# schematic1.net
KiCad netlist of a schematic drawn in EAGLE
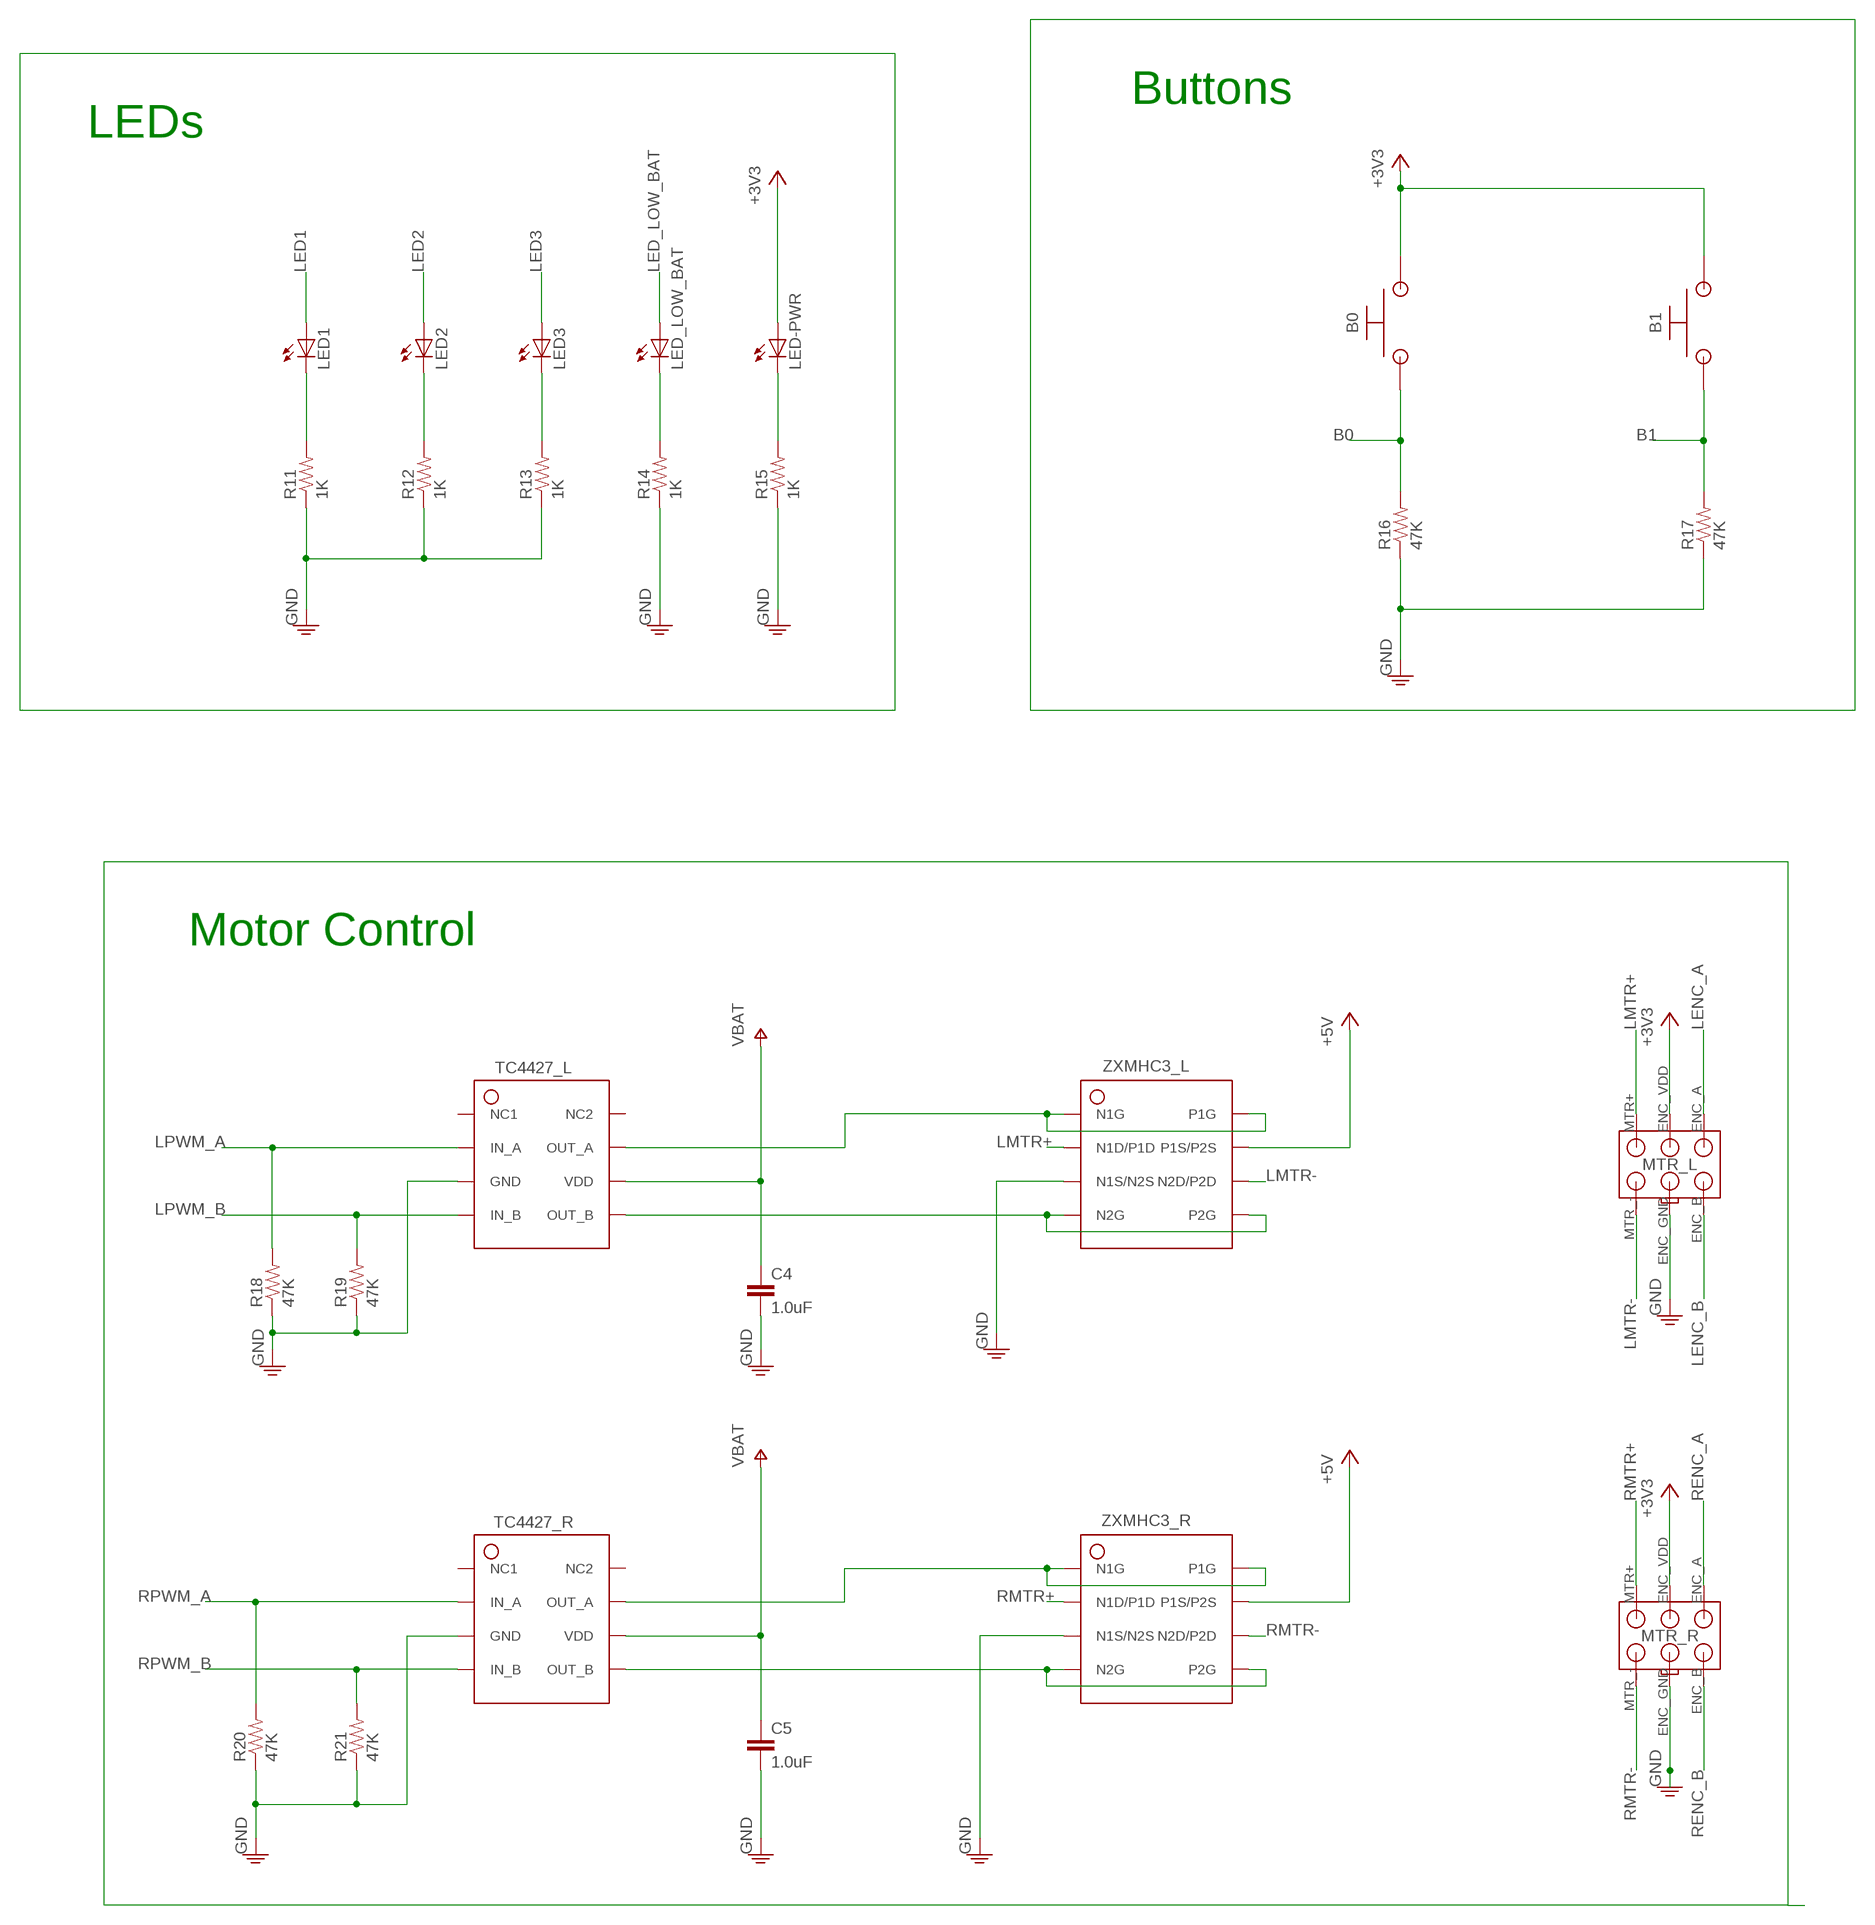
[diagram p0: schematic, sheet 1]

(export (version "E")
  (design (tool "Eeschema 10.0.6"))
  (components
    (comp (ref "B0")
      (value "POLOLU_BUTTON")
      (footprint "eagle-import:POLOLU_BUTTON")
      (libsource (lib "eagle-import") (part "POLOLU_BUTTON"))
    )
    (comp (ref "B1")
      (value "POLOLU_BUTTON")
      (footprint "eagle-import:POLOLU_BUTTON")
      (libsource (lib "eagle-import") (part "POLOLU_BUTTON"))
    )
    (comp (ref "C4")
      (value "1.0uF")
      (footprint "eagle-import:0805")
      (libsource (lib "eagle-import") (part "CAP_CERAMIC_0805IN_2012MM"))
    )
    (comp (ref "C5")
      (value "1.0uF")
      (footprint "eagle-import:0805")
      (libsource (lib "eagle-import") (part "CAP_CERAMIC_0805IN_2012MM"))
    )
    (comp (ref "LED-PWR")
      (value "LED")
      (footprint "eagle-import:LED-0805")
      (libsource (lib "eagle-import") (part "LED"))
    )
    (comp (ref "LED1")
      (value "LED")
      (footprint "eagle-import:LED-0805")
      (libsource (lib "eagle-import") (part "LED"))
    )
    (comp (ref "LED2")
      (value "LED")
      (footprint "eagle-import:LED-0805")
      (libsource (lib "eagle-import") (part "LED"))
    )
    (comp (ref "LED3")
      (value "LED")
      (footprint "eagle-import:LED-0805")
      (libsource (lib "eagle-import") (part "LED"))
    )
    (comp (ref "LED_LOW_BAT")
      (value "LED")
      (footprint "eagle-import:LED-0805")
      (libsource (lib "eagle-import") (part "LED"))
    )
    (comp (ref "MTR_L")
      (value "MOTOR_ENCODER_HEADER")
      (footprint "eagle-import:MOTOR_ENCODER_HEADER")
      (libsource (lib "eagle-import") (part "MOTOR_ENCODER_HEADER"))
    )
    (comp (ref "MTR_R")
      (value "MOTOR_ENCODER_HEADER")
      (footprint "eagle-import:MOTOR_ENCODER_HEADER")
      (libsource (lib "eagle-import") (part "MOTOR_ENCODER_HEADER"))
    )
    (comp (ref "R11")
      (value "1K")
      (footprint "eagle-import:0805")
      (libsource (lib "eagle-import") (part "RESISTOR_0805IN_2012MM"))
    )
    (comp (ref "R12")
      (value "1K")
      (footprint "eagle-import:0805")
      (libsource (lib "eagle-import") (part "RESISTOR_0805IN_2012MM"))
    )
    (comp (ref "R13")
      (value "1K")
      (footprint "eagle-import:0805")
      (libsource (lib "eagle-import") (part "RESISTOR_0805IN_2012MM"))
    )
    (comp (ref "R14")
      (value "1K")
      (footprint "eagle-import:0805")
      (libsource (lib "eagle-import") (part "RESISTOR_0805IN_2012MM"))
    )
    (comp (ref "R15")
      (value "1K")
      (footprint "eagle-import:0805")
      (libsource (lib "eagle-import") (part "RESISTOR_0805IN_2012MM"))
    )
    (comp (ref "R16")
      (value "47K")
      (footprint "eagle-import:0805")
      (libsource (lib "eagle-import") (part "RESISTOR_0805IN_2012MM"))
    )
    (comp (ref "R17")
      (value "47K")
      (footprint "eagle-import:0805")
      (libsource (lib "eagle-import") (part "RESISTOR_0805IN_2012MM"))
    )
    (comp (ref "R18")
      (value "47K")
      (footprint "eagle-import:0805")
      (libsource (lib "eagle-import") (part "RESISTOR_0805IN_2012MM"))
    )
    (comp (ref "R19")
      (value "47K")
      (footprint "eagle-import:0805")
      (libsource (lib "eagle-import") (part "RESISTOR_0805IN_2012MM"))
    )
    (comp (ref "R20")
      (value "47K")
      (footprint "eagle-import:0805")
      (libsource (lib "eagle-import") (part "RESISTOR_0805IN_2012MM"))
    )
    (comp (ref "R21")
      (value "47K")
      (footprint "eagle-import:0805")
      (libsource (lib "eagle-import") (part "RESISTOR_0805IN_2012MM"))
    )
    (comp (ref "TC4427_L")
      (value "TC4427_SOIC8")
      (footprint "eagle-import:TC4427_SOIC8")
      (libsource (lib "eagle-import") (part "TC4427_SOIC8"))
    )
    (comp (ref "TC4427_R")
      (value "TC4427_SOIC8")
      (footprint "eagle-import:TC4427_SOIC8")
      (libsource (lib "eagle-import") (part "TC4427_SOIC8"))
    )
    (comp (ref "ZXMHC3_L")
      (value "ZXMHC3")
      (footprint "eagle-import:ZXMHC3")
      (libsource (lib "eagle-import") (part "ZXMHC3"))
    )
    (comp (ref "ZXMHC3_R")
      (value "ZXMHC3")
      (footprint "eagle-import:ZXMHC3")
      (libsource (lib "eagle-import") (part "ZXMHC3"))
    )
  )
  (nets
    (net (code "1") (name "+3V3") (class "Default")
      (node (ref "B0") (pin "P$2") (pinfunction "2_P$2") (pintype "bidirectional"))
      (node (ref "B1") (pin "P$2") (pinfunction "2_P$2") (pintype "bidirectional"))
      (node (ref "LED-PWR") (pin "A") (pinfunction "A_A") (pintype "passive"))
      (node (ref "MTR_L") (pin "ENC_VDD") (pinfunction "ENC_VDD_ENC_VDD") (pintype "power_in"))
      (node (ref "MTR_R") (pin "ENC_VDD") (pinfunction "ENC_VDD_ENC_VDD") (pintype "power_in"))
    )
    (net (code "2") (name "+5V") (class "Default")
      (node (ref "ZXMHC3_L") (pin "P1S/P2S") (pinfunction "P1S/P2S_P1S/P2S") (pintype "bidirectional"))
      (node (ref "ZXMHC3_R") (pin "P1S/P2S") (pinfunction "P1S/P2S_P1S/P2S") (pintype "bidirectional"))
    )
    (net (code "3") (name "/B0") (class "Default")
      (node (ref "B0") (pin "P$1") (pinfunction "1_P$1") (pintype "bidirectional"))
      (node (ref "R16") (pin "2") (pinfunction "2_2") (pintype "passive"))
    )
    (net (code "4") (name "/B1") (class "Default")
      (node (ref "B1") (pin "P$1") (pinfunction "1_P$1") (pintype "bidirectional"))
      (node (ref "R17") (pin "2") (pinfunction "2_2") (pintype "passive"))
    )
    (net (code "5") (name "/LED1") (class "Default")
      (node (ref "LED1") (pin "A") (pinfunction "A_A") (pintype "passive"))
    )
    (net (code "6") (name "/LED2") (class "Default")
      (node (ref "LED2") (pin "A") (pinfunction "A_A") (pintype "passive"))
    )
    (net (code "7") (name "/LED3") (class "Default")
      (node (ref "LED3") (pin "A") (pinfunction "A_A") (pintype "passive"))
    )
    (net (code "8") (name "/LED_LOW_BAT") (class "Default")
      (node (ref "LED_LOW_BAT") (pin "A") (pinfunction "A_A") (pintype "passive"))
    )
    (net (code "9") (name "/LENC_A") (class "Default")
      (node (ref "MTR_L") (pin "ENC_A") (pinfunction "ENC_A_ENC_A") (pintype "output"))
    )
    (net (code "10") (name "/LENC_B") (class "Default")
      (node (ref "MTR_L") (pin "ENC_B") (pinfunction "ENC_B_ENC_B") (pintype "output"))
    )
    (net (code "11") (name "/LMTR+") (class "Default")
      (node (ref "MTR_L") (pin "MTR+") (pinfunction "MTR_+_MTR+") (pintype "input"))
      (node (ref "ZXMHC3_L") (pin "N1D/P1D") (pinfunction "N1D/P1D_N1D/P1D") (pintype "bidirectional"))
    )
    (net (code "12") (name "/LMTR-") (class "Default")
      (node (ref "MTR_L") (pin "MTR_-") (pinfunction "MTR_-_MTR_-") (pintype "input"))
      (node (ref "ZXMHC3_L") (pin "N2D/P2D") (pinfunction "N2D/P2D_N2D/P2D") (pintype "bidirectional"))
    )
    (net (code "13") (name "/LPWM_A") (class "Default")
      (node (ref "R18") (pin "2") (pinfunction "2_2") (pintype "passive"))
      (node (ref "TC4427_L") (pin "IN_A") (pinfunction "IN_A_IN_A") (pintype "bidirectional"))
    )
    (net (code "14") (name "/LPWM_B") (class "Default")
      (node (ref "R19") (pin "2") (pinfunction "2_2") (pintype "passive"))
      (node (ref "TC4427_L") (pin "IN_B") (pinfunction "IN_B_IN_B") (pintype "bidirectional"))
    )
    (net (code "15") (name "/RENC_A") (class "Default")
      (node (ref "MTR_R") (pin "ENC_A") (pinfunction "ENC_A_ENC_A") (pintype "output"))
    )
    (net (code "16") (name "/RENC_B") (class "Default")
      (node (ref "MTR_R") (pin "ENC_B") (pinfunction "ENC_B_ENC_B") (pintype "output"))
    )
    (net (code "17") (name "/RMTR+") (class "Default")
      (node (ref "MTR_R") (pin "MTR+") (pinfunction "MTR_+_MTR+") (pintype "input"))
      (node (ref "ZXMHC3_R") (pin "N1D/P1D") (pinfunction "N1D/P1D_N1D/P1D") (pintype "bidirectional"))
    )
    (net (code "18") (name "/RMTR-") (class "Default")
      (node (ref "MTR_R") (pin "MTR_-") (pinfunction "MTR_-_MTR_-") (pintype "input"))
      (node (ref "ZXMHC3_R") (pin "N2D/P2D") (pinfunction "N2D/P2D_N2D/P2D") (pintype "bidirectional"))
    )
    (net (code "19") (name "/RPWM_A") (class "Default")
      (node (ref "R20") (pin "2") (pinfunction "2_2") (pintype "passive"))
      (node (ref "TC4427_R") (pin "IN_A") (pinfunction "IN_A_IN_A") (pintype "bidirectional"))
    )
    (net (code "20") (name "/RPWM_B") (class "Default")
      (node (ref "R21") (pin "2") (pinfunction "2_2") (pintype "passive"))
      (node (ref "TC4427_R") (pin "IN_B") (pinfunction "IN_B_IN_B") (pintype "bidirectional"))
    )
    (net (code "21") (name "GND") (class "Default")
      (node (ref "C4") (pin "2") (pinfunction "2_2") (pintype "passive"))
      (node (ref "C5") (pin "2") (pinfunction "2_2") (pintype "passive"))
      (node (ref "MTR_L") (pin "ENC_GND") (pinfunction "ENC_GND_ENC_GND") (pintype "power_in"))
      (node (ref "MTR_R") (pin "ENC_GND") (pinfunction "ENC_GND_ENC_GND") (pintype "power_in"))
      (node (ref "R11") (pin "1") (pinfunction "1_1") (pintype "passive"))
      (node (ref "R12") (pin "1") (pinfunction "1_1") (pintype "passive"))
      (node (ref "R13") (pin "1") (pinfunction "1_1") (pintype "passive"))
      (node (ref "R14") (pin "1") (pinfunction "1_1") (pintype "passive"))
      (node (ref "R15") (pin "1") (pinfunction "1_1") (pintype "passive"))
      (node (ref "R16") (pin "1") (pinfunction "1_1") (pintype "passive"))
      (node (ref "R17") (pin "1") (pinfunction "1_1") (pintype "passive"))
      (node (ref "R18") (pin "1") (pinfunction "1_1") (pintype "passive"))
      (node (ref "R19") (pin "1") (pinfunction "1_1") (pintype "passive"))
      (node (ref "R20") (pin "1") (pinfunction "1_1") (pintype "passive"))
      (node (ref "R21") (pin "1") (pinfunction "1_1") (pintype "passive"))
      (node (ref "TC4427_L") (pin "GND") (pinfunction "GND_GND") (pintype "power_in"))
      (node (ref "TC4427_R") (pin "GND") (pinfunction "GND_GND") (pintype "power_in"))
      (node (ref "ZXMHC3_L") (pin "N1S/N2S") (pinfunction "N1S/N2S_N1S/N2S") (pintype "bidirectional"))
      (node (ref "ZXMHC3_R") (pin "N1S/N2S") (pinfunction "N1S/N2S_N1S/N2S") (pintype "bidirectional"))
    )
    (net (code "22") (name "Net-(LED-PWR-PadC)") (class "Default")
      (node (ref "LED-PWR") (pin "C") (pinfunction "C_C") (pintype "passive"))
      (node (ref "R15") (pin "2") (pinfunction "2_2") (pintype "passive"))
    )
    (net (code "23") (name "Net-(LED1-PadC)") (class "Default")
      (node (ref "LED1") (pin "C") (pinfunction "C_C") (pintype "passive"))
      (node (ref "R11") (pin "2") (pinfunction "2_2") (pintype "passive"))
    )
    (net (code "24") (name "Net-(LED2-PadC)") (class "Default")
      (node (ref "LED2") (pin "C") (pinfunction "C_C") (pintype "passive"))
      (node (ref "R12") (pin "2") (pinfunction "2_2") (pintype "passive"))
    )
    (net (code "25") (name "Net-(LED3-PadC)") (class "Default")
      (node (ref "LED3") (pin "C") (pinfunction "C_C") (pintype "passive"))
      (node (ref "R13") (pin "2") (pinfunction "2_2") (pintype "passive"))
    )
    (net (code "26") (name "Net-(LED_LOW_BAT-PadC)") (class "Default")
      (node (ref "LED_LOW_BAT") (pin "C") (pinfunction "C_C") (pintype "passive"))
      (node (ref "R14") (pin "2") (pinfunction "2_2") (pintype "passive"))
    )
    (net (code "27") (name "Net-(TC4427_L-PadOUT_A)") (class "Default")
      (node (ref "TC4427_L") (pin "OUT_A") (pinfunction "OUT_A_OUT_A") (pintype "bidirectional"))
      (node (ref "ZXMHC3_L") (pin "N1G") (pinfunction "N1G_N1G") (pintype "bidirectional"))
      (node (ref "ZXMHC3_L") (pin "P1G") (pinfunction "P1G_P1G") (pintype "bidirectional"))
    )
    (net (code "28") (name "Net-(TC4427_L-PadOUT_B)") (class "Default")
      (node (ref "TC4427_L") (pin "OUT_B") (pinfunction "OUT_B_OUT_B") (pintype "bidirectional"))
      (node (ref "ZXMHC3_L") (pin "N2G") (pinfunction "N2G_N2G") (pintype "bidirectional"))
      (node (ref "ZXMHC3_L") (pin "P2G") (pinfunction "P2G_P2G") (pintype "bidirectional"))
    )
    (net (code "29") (name "Net-(TC4427_R-PadOUT_A)") (class "Default")
      (node (ref "TC4427_R") (pin "OUT_A") (pinfunction "OUT_A_OUT_A") (pintype "bidirectional"))
      (node (ref "ZXMHC3_R") (pin "N1G") (pinfunction "N1G_N1G") (pintype "bidirectional"))
      (node (ref "ZXMHC3_R") (pin "P1G") (pinfunction "P1G_P1G") (pintype "bidirectional"))
    )
    (net (code "30") (name "Net-(TC4427_R-PadOUT_B)") (class "Default")
      (node (ref "TC4427_R") (pin "OUT_B") (pinfunction "OUT_B_OUT_B") (pintype "bidirectional"))
      (node (ref "ZXMHC3_R") (pin "N2G") (pinfunction "N2G_N2G") (pintype "bidirectional"))
      (node (ref "ZXMHC3_R") (pin "P2G") (pinfunction "P2G_P2G") (pintype "bidirectional"))
    )
    (net (code "31") (name "VBAT") (class "Default")
      (node (ref "C4") (pin "1") (pinfunction "1_1") (pintype "passive"))
      (node (ref "C5") (pin "1") (pinfunction "1_1") (pintype "passive"))
      (node (ref "TC4427_L") (pin "VDD") (pinfunction "VDD_VDD") (pintype "power_in"))
      (node (ref "TC4427_R") (pin "VDD") (pinfunction "VDD_VDD") (pintype "power_in"))
    )
    (net (code "32") (name "unconnected-(TC4427_L-PadNC1)") (class "Default")
      (node (ref "TC4427_L") (pin "NC1") (pinfunction "NC1_NC1") (pintype "bidirectional"))
    )
    (net (code "33") (name "unconnected-(TC4427_L-PadNC2)") (class "Default")
      (node (ref "TC4427_L") (pin "NC2") (pinfunction "NC2_NC2") (pintype "bidirectional"))
    )
    (net (code "34") (name "unconnected-(TC4427_R-PadNC1)") (class "Default")
      (node (ref "TC4427_R") (pin "NC1") (pinfunction "NC1_NC1") (pintype "bidirectional"))
    )
    (net (code "35") (name "unconnected-(TC4427_R-PadNC2)") (class "Default")
      (node (ref "TC4427_R") (pin "NC2") (pinfunction "NC2_NC2") (pintype "bidirectional"))
    )
  )
)
